# 03_MCU.net
KiCad netlist of a schematic drawn in Altium Designer
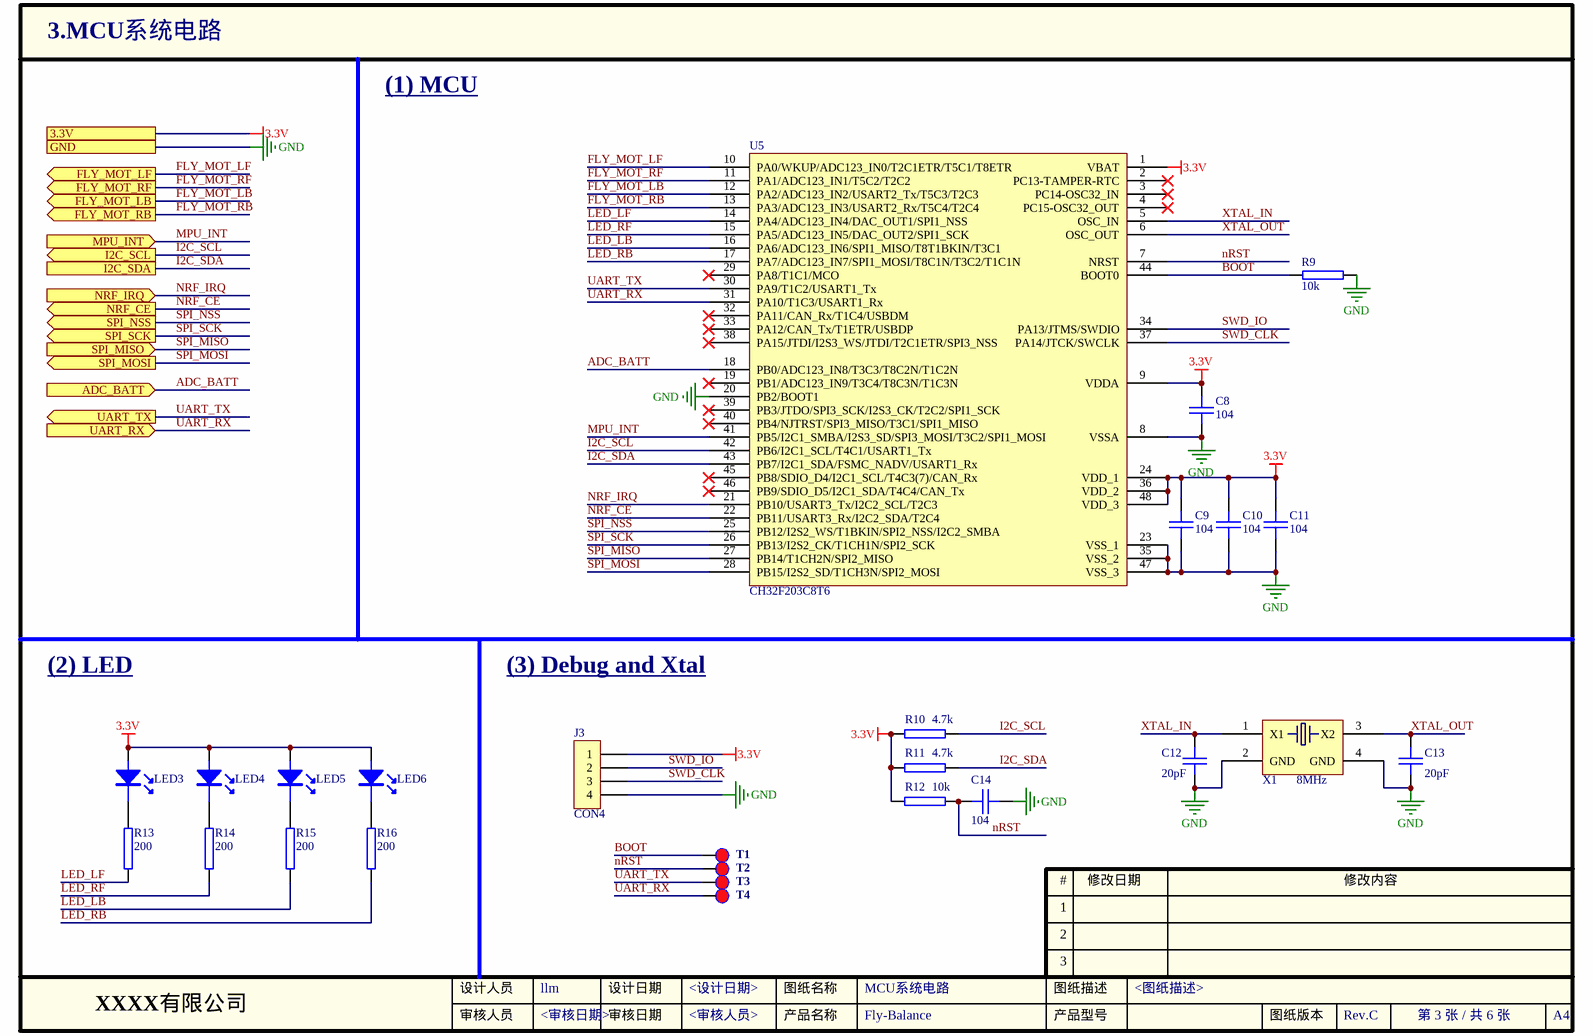
[diagram p0: 03_MCU.SchDoc]

(export (version "E")
  (design (tool "Eeschema 10.0.6"))
  (components
    (comp (ref "C8")
      (value "104")
      (footprint "0402C")
      (description "电容")
      (libsource (lib "MY_Schlib") (part "CAP"))
    )
    (comp (ref "C9")
      (value "104")
      (footprint "0402C")
      (description "电容")
      (libsource (lib "MY_Schlib") (part "CAP"))
    )
    (comp (ref "C10")
      (value "104")
      (footprint "0402C")
      (description "电容")
      (libsource (lib "MY_Schlib") (part "CAP"))
    )
    (comp (ref "C11")
      (value "104")
      (footprint "0402C")
      (description "电容")
      (libsource (lib "MY_Schlib") (part "CAP"))
    )
    (comp (ref "C12")
      (value "20pF")
      (footprint "0402C")
      (description "电容")
      (libsource (lib "MY_Schlib") (part "CAP"))
    )
    (comp (ref "C13")
      (value "20pF")
      (footprint "0402C")
      (description "电容")
      (libsource (lib "MY_Schlib") (part "CAP"))
    )
    (comp (ref "C14")
      (value "104")
      (footprint "0402C")
      (description "电容")
      (libsource (lib "MY_Schlib") (part "CAP"))
    )
    (comp (ref "J3")
      (value "CON4")
      (footprint "SIP-4-2.54")
      (description "Connector")
      (libsource (lib "MY_Schlib") (part "CON4"))
    )
    (comp (ref "LED3")
      (value "Blue")
      (footprint "LED-0603")
      (description "发光二极管")
      (libsource (lib "MY_Schlib") (part "LED"))
    )
    (comp (ref "LED4")
      (value "Blue")
      (footprint "LED-0603")
      (description "发光二极管")
      (libsource (lib "MY_Schlib") (part "LED"))
    )
    (comp (ref "LED5")
      (value "Blue")
      (footprint "LED-0603")
      (description "发光二极管")
      (libsource (lib "MY_Schlib") (part "LED"))
    )
    (comp (ref "LED6")
      (value "Blue")
      (footprint "LED-0603")
      (description "发光二极管")
      (libsource (lib "MY_Schlib") (part "LED"))
    )
    (comp (ref "R9")
      (value "10k")
      (footprint "0402R")
      (description "电阻")
      (libsource (lib "MY_Schlib") (part "RES"))
    )
    (comp (ref "R10")
      (value "4.7k")
      (footprint "0402R")
      (description "电阻")
      (libsource (lib "MY_Schlib") (part "RES"))
    )
    (comp (ref "R11")
      (value "4.7k")
      (footprint "0402R")
      (description "电阻")
      (libsource (lib "MY_Schlib") (part "RES"))
    )
    (comp (ref "R12")
      (value "10k")
      (footprint "0402R")
      (description "电阻")
      (libsource (lib "MY_Schlib") (part "RES"))
    )
    (comp (ref "R13")
      (value "200")
      (footprint "0402R")
      (description "电阻")
      (libsource (lib "MY_Schlib") (part "RES"))
    )
    (comp (ref "R14")
      (value "200")
      (footprint "0402R")
      (description "电阻")
      (libsource (lib "MY_Schlib") (part "RES"))
    )
    (comp (ref "R15")
      (value "200")
      (footprint "0402R")
      (description "电阻")
      (libsource (lib "MY_Schlib") (part "RES"))
    )
    (comp (ref "R16")
      (value "200")
      (footprint "0402R")
      (description "电阻")
      (libsource (lib "MY_Schlib") (part "RES"))
    )
    (comp (ref "T1")
      (value "BOOT")
      (footprint "PAD-40")
      (description "测试点")
      (libsource (lib "MY_Schlib") (part "TEST-DOT"))
    )
    (comp (ref "T2")
      (value "RST")
      (footprint "PAD-40")
      (description "测试点")
      (libsource (lib "MY_Schlib") (part "TEST-DOT"))
    )
    (comp (ref "T3")
      (value "Tx")
      (footprint "PAD-40")
      (description "测试点")
      (libsource (lib "MY_Schlib") (part "TEST-DOT"))
    )
    (comp (ref "T4")
      (value "Rx")
      (footprint "PAD-40")
      (description "测试点")
      (libsource (lib "MY_Schlib") (part "TEST-DOT"))
    )
    (comp (ref "U5")
      (value "CH32F203C8T6")
      (footprint "LQFP-48_7x7")
      (description "STM32单片机48引脚")
      (libsource (lib "MY_Schlib") (part "STM32F103C"))
    )
    (comp (ref "X1")
      (value "8MHz")
      (footprint "OSCCC250X320X80-4N")
      (description "4pin贴片无源晶振")
      (libsource (lib "MY_Schlib") (part "XTAL4"))
    )
  )
  (nets
    (net (code "1") (name "/ADC_BATT") (class "Default")
      (node (ref "U5") (pin "18") (pinfunction "PB0/ADC123_IN8/T3C3/T8C2N/T1C2N_18") (pintype "passive"))
    )
    (net (code "2") (name "/BOOT") (class "Default")
      (node (ref "R9") (pin "1") (pinfunction "1_1") (pintype "passive"))
      (node (ref "T1") (pin "1") (pinfunction "1_1") (pintype "passive"))
      (node (ref "U5") (pin "44") (pinfunction "BOOT0_44") (pintype "passive"))
    )
    (net (code "3") (name "/FLY_MOT_LB") (class "Default")
      (node (ref "U5") (pin "12") (pinfunction "PA2/ADC123_IN2/USART2_Tx/T5C3/T2C3_12") (pintype "passive"))
    )
    (net (code "4") (name "/FLY_MOT_LF") (class "Default")
      (node (ref "U5") (pin "10") (pinfunction "PA0/WKUP/ADC123_IN0/T2C1ETR/T5C1/T8ETR_10") (pintype "passive"))
    )
    (net (code "5") (name "/FLY_MOT_RB") (class "Default")
      (node (ref "U5") (pin "13") (pinfunction "PA3/ADC123_IN3/USART2_Rx/T5C4/T2C4_13") (pintype "passive"))
    )
    (net (code "6") (name "/FLY_MOT_RF") (class "Default")
      (node (ref "U5") (pin "11") (pinfunction "PA1/ADC123_IN1/T5C2/T2C2_11") (pintype "passive"))
    )
    (net (code "7") (name "/I2C_SCL") (class "Default")
      (node (ref "R10") (pin "1") (pinfunction "1_1") (pintype "passive"))
      (node (ref "U5") (pin "42") (pinfunction "PB6/I2C1_SCL/T4C1/USART1_Tx_42") (pintype "passive"))
    )
    (net (code "8") (name "/I2C_SDA") (class "Default")
      (node (ref "R11") (pin "1") (pinfunction "1_1") (pintype "passive"))
      (node (ref "U5") (pin "43") (pinfunction "PB7/I2C1_SDA/FSMC_NADV/USART1_Rx_43") (pintype "passive"))
    )
    (net (code "9") (name "/LED_LB") (class "Default")
      (node (ref "R15") (pin "1") (pinfunction "1_1") (pintype "passive"))
      (node (ref "U5") (pin "16") (pinfunction "PA6/ADC123_IN6/SPI1_MISO/T8T1BKIN/T3C1_16") (pintype "passive"))
    )
    (net (code "10") (name "/LED_LF") (class "Default")
      (node (ref "R13") (pin "1") (pinfunction "1_1") (pintype "passive"))
      (node (ref "U5") (pin "14") (pinfunction "PA4/ADC123_IN4/DAC_OUT1/SPI1_NSS_14") (pintype "passive"))
    )
    (net (code "11") (name "/LED_RB") (class "Default")
      (node (ref "R16") (pin "1") (pinfunction "1_1") (pintype "passive"))
      (node (ref "U5") (pin "17") (pinfunction "PA7/ADC123_IN7/SPI1_MOSI/T8C1N/T3C2/T1C1N_17") (pintype "passive"))
    )
    (net (code "12") (name "/LED_RF") (class "Default")
      (node (ref "R14") (pin "1") (pinfunction "1_1") (pintype "passive"))
      (node (ref "U5") (pin "15") (pinfunction "PA5/ADC123_IN5/DAC_OUT2/SPI1_SCK_15") (pintype "passive"))
    )
    (net (code "13") (name "/MPU_INT") (class "Default")
      (node (ref "U5") (pin "41") (pinfunction "PB5/I2C1_SMBA/I2S3_SD/SPI3_MOSI/T3C2/SPI1_MOSI_41") (pintype "passive"))
    )
    (net (code "14") (name "/NRF_CE") (class "Default")
      (node (ref "U5") (pin "22") (pinfunction "PB11/USART3_Rx/I2C2_SDA/T2C4_22") (pintype "passive"))
    )
    (net (code "15") (name "/NRF_IRQ") (class "Default")
      (node (ref "U5") (pin "21") (pinfunction "PB10/USART3_Tx/I2C2_SCL/T2C3_21") (pintype "passive"))
    )
    (net (code "16") (name "/SPI_MISO") (class "Default")
      (node (ref "U5") (pin "27") (pinfunction "PB14/T1CH2N/SPI2_MISO_27") (pintype "passive"))
    )
    (net (code "17") (name "/SPI_MOSI") (class "Default")
      (node (ref "U5") (pin "28") (pinfunction "PB15/I2S2_SD/T1CH3N/SPI2_MOSI_28") (pintype "passive"))
    )
    (net (code "18") (name "/SPI_NSS") (class "Default")
      (node (ref "U5") (pin "25") (pinfunction "PB12/I2S2_WS/T1BKIN/SPI2_NSS/I2C2_SMBA_25") (pintype "passive"))
    )
    (net (code "19") (name "/SPI_SCK") (class "Default")
      (node (ref "U5") (pin "26") (pinfunction "PB13/I2S2_CK/T1CH1N/SPI2_SCK_26") (pintype "passive"))
    )
    (net (code "20") (name "/SWD_CLK") (class "Default")
      (node (ref "J3") (pin "3") (pinfunction "3_3") (pintype "passive"))
      (node (ref "U5") (pin "37") (pinfunction "PA14/JTCK/SWCLK_37") (pintype "passive"))
    )
    (net (code "21") (name "/SWD_IO") (class "Default")
      (node (ref "J3") (pin "2") (pinfunction "2_2") (pintype "passive"))
      (node (ref "U5") (pin "34") (pinfunction "PA13/JTMS/SWDIO_34") (pintype "passive"))
    )
    (net (code "22") (name "/UART_RX") (class "Default")
      (node (ref "T4") (pin "1") (pinfunction "1_1") (pintype "passive"))
      (node (ref "U5") (pin "31") (pinfunction "PA10/T1C3/USART1_Rx_31") (pintype "passive"))
    )
    (net (code "23") (name "/UART_TX") (class "Default")
      (node (ref "T3") (pin "1") (pinfunction "1_1") (pintype "passive"))
      (node (ref "U5") (pin "30") (pinfunction "PA9/T1C2/USART1_Tx_30") (pintype "passive"))
    )
    (net (code "24") (name "/XTAL_IN") (class "Default")
      (node (ref "C12") (pin "2") (pinfunction "2_2") (pintype "passive"))
      (node (ref "U5") (pin "5") (pinfunction "OSC_IN_5") (pintype "passive"))
      (node (ref "X1") (pin "1") (pinfunction "X1_1") (pintype "passive"))
    )
    (net (code "25") (name "/XTAL_OUT") (class "Default")
      (node (ref "C13") (pin "2") (pinfunction "2_2") (pintype "passive"))
      (node (ref "U5") (pin "6") (pinfunction "OSC_OUT_6") (pintype "passive"))
      (node (ref "X1") (pin "3") (pinfunction "X2_3") (pintype "passive"))
    )
    (net (code "26") (name "/nRST") (class "Default")
      (node (ref "C14") (pin "2") (pinfunction "2_2") (pintype "passive"))
      (node (ref "R12") (pin "1") (pinfunction "1_1") (pintype "passive"))
      (node (ref "T2") (pin "1") (pinfunction "1_1") (pintype "passive"))
      (node (ref "U5") (pin "7") (pinfunction "NRST_7") (pintype "passive"))
    )
    (net (code "27") (name "3.3V") (class "Default")
      (node (ref "C10") (pin "2") (pinfunction "2_2") (pintype "passive"))
      (node (ref "C11") (pin "2") (pinfunction "2_2") (pintype "passive"))
      (node (ref "C8") (pin "2") (pinfunction "2_2") (pintype "passive"))
      (node (ref "C9") (pin "2") (pinfunction "2_2") (pintype "passive"))
      (node (ref "J3") (pin "1") (pinfunction "1_1") (pintype "passive"))
      (node (ref "LED3") (pin "1") (pinfunction "1_1") (pintype "passive"))
      (node (ref "LED4") (pin "1") (pinfunction "1_1") (pintype "passive"))
      (node (ref "LED5") (pin "1") (pinfunction "1_1") (pintype "passive"))
      (node (ref "LED6") (pin "1") (pinfunction "1_1") (pintype "passive"))
      (node (ref "R10") (pin "2") (pinfunction "2_2") (pintype "passive"))
      (node (ref "R11") (pin "2") (pinfunction "2_2") (pintype "passive"))
      (node (ref "R12") (pin "2") (pinfunction "2_2") (pintype "passive"))
      (node (ref "U5") (pin "1") (pinfunction "VBAT_1") (pintype "passive"))
      (node (ref "U5") (pin "24") (pinfunction "VDD_1_24") (pintype "passive"))
      (node (ref "U5") (pin "36") (pinfunction "VDD_2_36") (pintype "passive"))
      (node (ref "U5") (pin "48") (pinfunction "VDD_3_48") (pintype "passive"))
      (node (ref "U5") (pin "9") (pinfunction "VDDA_9") (pintype "passive"))
    )
    (net (code "28") (name "GND") (class "Default")
      (node (ref "C10") (pin "1") (pinfunction "1_1") (pintype "passive"))
      (node (ref "C11") (pin "1") (pinfunction "1_1") (pintype "passive"))
      (node (ref "C12") (pin "1") (pinfunction "1_1") (pintype "passive"))
      (node (ref "C13") (pin "1") (pinfunction "1_1") (pintype "passive"))
      (node (ref "C14") (pin "1") (pinfunction "1_1") (pintype "passive"))
      (node (ref "C8") (pin "1") (pinfunction "1_1") (pintype "passive"))
      (node (ref "C9") (pin "1") (pinfunction "1_1") (pintype "passive"))
      (node (ref "J3") (pin "4") (pinfunction "4_4") (pintype "passive"))
      (node (ref "R9") (pin "2") (pinfunction "2_2") (pintype "passive"))
      (node (ref "U5") (pin "20") (pinfunction "PB2/BOOT1_20") (pintype "passive"))
      (node (ref "U5") (pin "23") (pinfunction "VSS_1_23") (pintype "passive"))
      (node (ref "U5") (pin "35") (pinfunction "VSS_2_35") (pintype "passive"))
      (node (ref "U5") (pin "47") (pinfunction "VSS_3_47") (pintype "passive"))
      (node (ref "U5") (pin "8") (pinfunction "VSSA_8") (pintype "passive"))
      (node (ref "X1") (pin "2") (pinfunction "GND_2") (pintype "passive"))
      (node (ref "X1") (pin "4") (pinfunction "GND_4") (pintype "passive"))
    )
    (net (code "29") (name "Net-(LED3-Pad2)") (class "Default")
      (node (ref "LED3") (pin "2") (pinfunction "2_2") (pintype "passive"))
      (node (ref "R13") (pin "2") (pinfunction "2_2") (pintype "passive"))
    )
    (net (code "30") (name "Net-(LED4-Pad2)") (class "Default")
      (node (ref "LED4") (pin "2") (pinfunction "2_2") (pintype "passive"))
      (node (ref "R14") (pin "2") (pinfunction "2_2") (pintype "passive"))
    )
    (net (code "31") (name "Net-(LED5-Pad2)") (class "Default")
      (node (ref "LED5") (pin "2") (pinfunction "2_2") (pintype "passive"))
      (node (ref "R15") (pin "2") (pinfunction "2_2") (pintype "passive"))
    )
    (net (code "32") (name "Net-(LED6-Pad2)") (class "Default")
      (node (ref "LED6") (pin "2") (pinfunction "2_2") (pintype "passive"))
      (node (ref "R16") (pin "2") (pinfunction "2_2") (pintype "passive"))
    )
    (net (code "33") (name "unconnected-(U5-PA8{slash}T1C1{slash}MCO-Pad29)") (class "Default")
      (node (ref "U5") (pin "29") (pinfunction "PA8/T1C1/MCO_29") (pintype "passive+no_connect"))
    )
    (net (code "34") (name "unconnected-(U5-PA11{slash}CAN_Rx{slash}T1C4{slash}USBDM-Pad32)") (class "Default")
      (node (ref "U5") (pin "32") (pinfunction "PA11/CAN_Rx/T1C4/USBDM_32") (pintype "passive+no_connect"))
    )
    (net (code "35") (name "unconnected-(U5-PA12{slash}CAN_Tx{slash}T1ETR{slash}USBDP-Pad33)") (class "Default")
      (node (ref "U5") (pin "33") (pinfunction "PA12/CAN_Tx/T1ETR/USBDP_33") (pintype "passive+no_connect"))
    )
    (net (code "36") (name "unconnected-(U5-PA15{slash}JTDI{slash}I2S3_WS{slash}JTDI{slash}T2C1ETR{slash}SPI3_NSS-Pad38)") (class "Default")
      (node (ref "U5") (pin "38") (pinfunction "PA15/JTDI/I2S3_WS/JTDI/T2C1ETR/SPI3_NSS_38") (pintype "passive+no_connect"))
    )
    (net (code "37") (name "unconnected-(U5-PB1{slash}ADC123_IN9{slash}T3C4{slash}T8C3N{slash}T1C3N-Pad19)") (class "Default")
      (node (ref "U5") (pin "19") (pinfunction "PB1/ADC123_IN9/T3C4/T8C3N/T1C3N_19") (pintype "passive+no_connect"))
    )
    (net (code "38") (name "unconnected-(U5-PB3{slash}JTDO{slash}SPI3_SCK{slash}I2S3_CK{slash}T2C2{slash}SPI1_SCK-Pad39)") (class "Default")
      (node (ref "U5") (pin "39") (pinfunction "PB3/JTDO/SPI3_SCK/I2S3_CK/T2C2/SPI1_SCK_39") (pintype "passive+no_connect"))
    )
    (net (code "39") (name "unconnected-(U5-PB4{slash}NJTRST{slash}SPI3_MISO{slash}T3C1{slash}SPI1_MISO-Pad40)") (class "Default")
      (node (ref "U5") (pin "40") (pinfunction "PB4/NJTRST/SPI3_MISO/T3C1/SPI1_MISO_40") (pintype "passive+no_connect"))
    )
    (net (code "40") (name "unconnected-(U5-PB8{slash}SDIO_D4{slash}I2C1_SCL{slash}T4C3(7){slash}CAN_Rx-Pad45)") (class "Default")
      (node (ref "U5") (pin "45") (pinfunction "PB8/SDIO_D4/I2C1_SCL/T4C3(7)/CAN_Rx_45") (pintype "passive+no_connect"))
    )
    (net (code "41") (name "unconnected-(U5-PB9{slash}SDIO_D5{slash}I2C1_SDA{slash}T4C4{slash}CAN_Tx-Pad46)") (class "Default")
      (node (ref "U5") (pin "46") (pinfunction "PB9/SDIO_D5/I2C1_SDA/T4C4/CAN_Tx_46") (pintype "passive+no_connect"))
    )
    (net (code "42") (name "unconnected-(U5-PC13-TAMPER-RTC-Pad2)") (class "Default")
      (node (ref "U5") (pin "2") (pinfunction "PC13-TAMPER-RTC_2") (pintype "passive+no_connect"))
    )
    (net (code "43") (name "unconnected-(U5-PC14-OSC32_IN-Pad3)") (class "Default")
      (node (ref "U5") (pin "3") (pinfunction "PC14-OSC32_IN_3") (pintype "passive+no_connect"))
    )
    (net (code "44") (name "unconnected-(U5-PC15-OSC32_OUT-Pad4)") (class "Default")
      (node (ref "U5") (pin "4") (pinfunction "PC15-OSC32_OUT_4") (pintype "passive+no_connect"))
    )
  )
)
